# Connections.net
KiCad netlist of a schematic drawn in Altium Designer
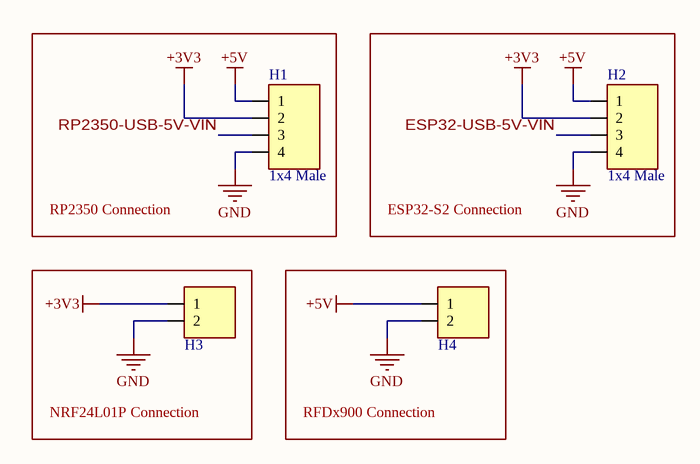
[diagram p0: Connections.SchDoc]

(export (version "E")
  (design (tool "Eeschema 10.0.6"))
  (components
    (comp (ref "H1")
      (value "1x4 Male")
      (footprint "[Header] Shrouded 1x4 Male")
      (description "70543-0003\r\nMates with 005057-9404")
      (libsource (lib "RADM Connectors") (part "[Header] Shrouded 1x4 Male"))
    )
    (comp (ref "H2")
      (value "1x4 Male")
      (footprint "[Header] Shrouded 1x4 Male")
      (description "70543-0003\r\nMates with 005057-9404")
      (libsource (lib "RADM Connectors") (part "[Header] Shrouded 1x4 Male"))
    )
    (comp (ref "H3")
      (value "1x2 Male")
      (footprint "[Header] Shrouded 1x2 Male")
      (description "0705430036\r\nMates with 0050579402")
      (libsource (lib "RADM Connectors") (part "[Header] Shrouded 1x2 Male"))
    )
    (comp (ref "H4")
      (value "1x2 Male")
      (footprint "[Header] Shrouded 1x2 Male")
      (description "0705430036\r\nMates with 0050579402")
      (libsource (lib "RADM Connectors") (part "[Header] Shrouded 1x2 Male"))
    )
  )
  (nets
    (net (code "1") (name "+3V3") (class "Default")
      (node (ref "H1") (pin "2") (pinfunction "2_2") (pintype "passive"))
      (node (ref "H2") (pin "2") (pinfunction "2_2") (pintype "passive"))
      (node (ref "H3") (pin "1") (pinfunction "1_1") (pintype "passive"))
    )
    (net (code "2") (name "+5V") (class "Default")
      (node (ref "H1") (pin "1") (pinfunction "1_1") (pintype "passive"))
      (node (ref "H2") (pin "1") (pinfunction "1_1") (pintype "passive"))
      (node (ref "H4") (pin "1") (pinfunction "1_1") (pintype "passive"))
    )
    (net (code "3") (name "/ESP32-USB-5V-VIN") (class "Default")
      (node (ref "H2") (pin "3") (pinfunction "3_3") (pintype "passive"))
    )
    (net (code "4") (name "/RP2350-USB-5V-VIN") (class "Default")
      (node (ref "H1") (pin "3") (pinfunction "3_3") (pintype "passive"))
    )
    (net (code "5") (name "GND") (class "Default")
      (node (ref "H1") (pin "4") (pinfunction "4_4") (pintype "passive"))
      (node (ref "H2") (pin "4") (pinfunction "4_4") (pintype "passive"))
      (node (ref "H3") (pin "2") (pinfunction "2_2") (pintype "passive"))
      (node (ref "H4") (pin "2") (pinfunction "2_2") (pintype "passive"))
    )
  )
)
